# Radio.net
KiCad netlist of a schematic drawn in Altium Designer
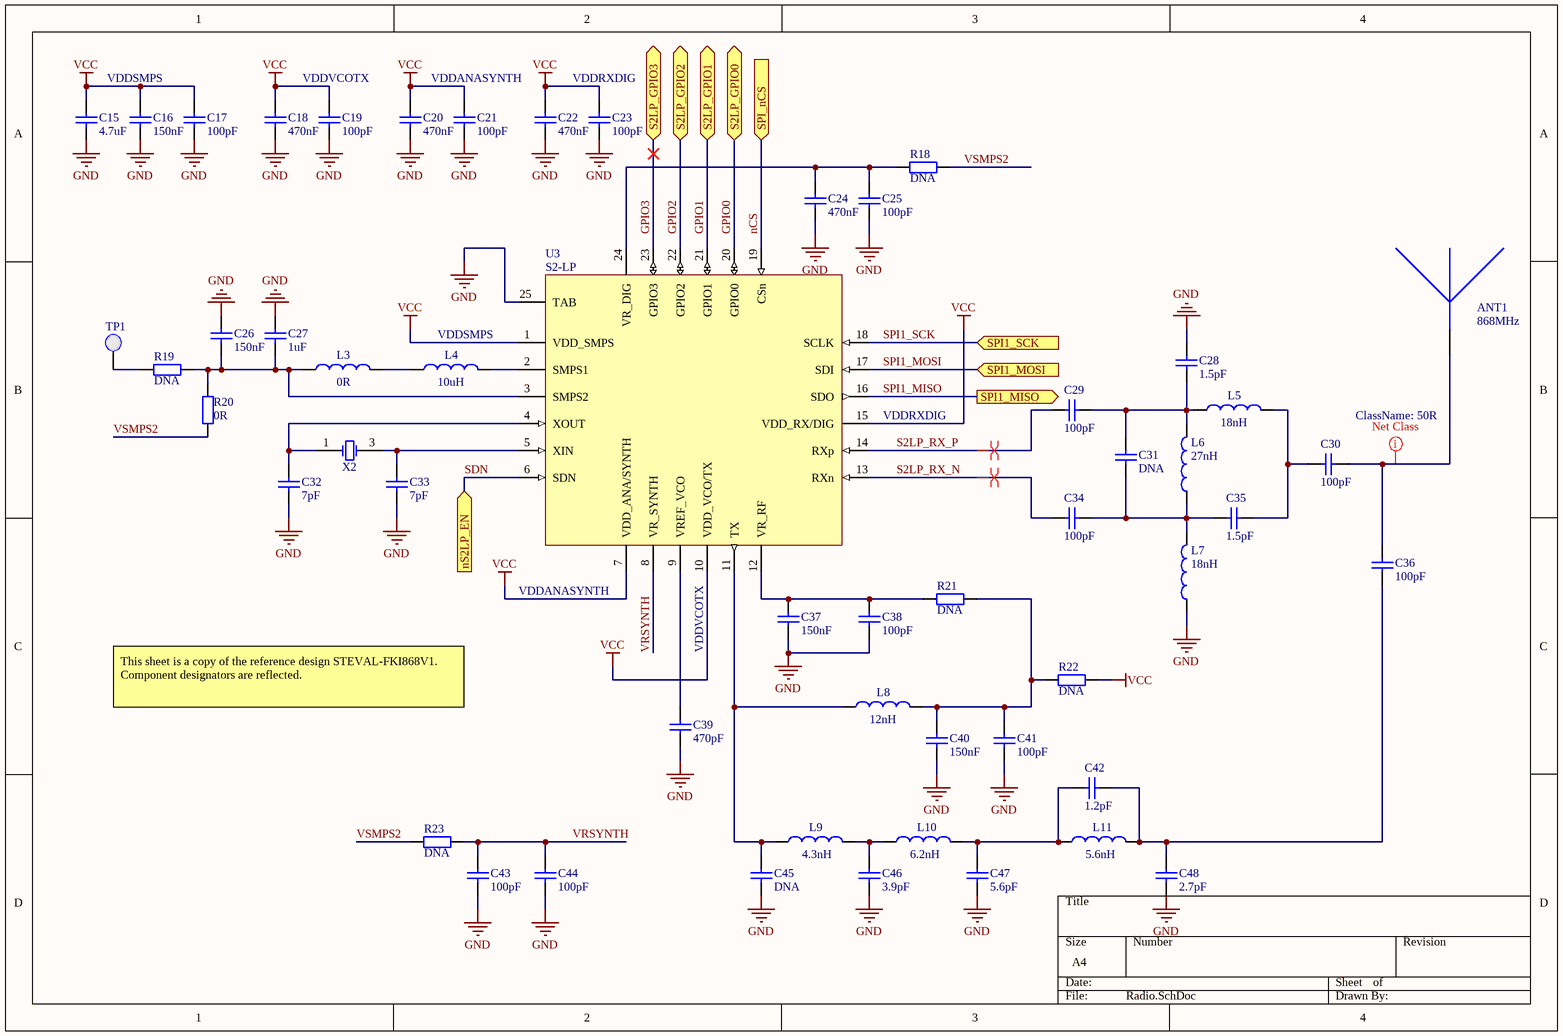
[diagram p0: Radio.SchDoc]

(export (version "E")
  (design (tool "Eeschema 10.0.6"))
  (components
    (comp (ref "ANT1")
      (value "868MHz")
      (footprint "ANTENNA")
      (libsource (lib "Light Sensor Node") (part "ANTENNA"))
    )
    (comp (ref "C15")
      (value "4.7uF")
      (footprint "C0603")
      (description "CAP")
      (fields
        (field (name "MANUFACTURER") "MURATA")
        (field (name "MANUFACTURER PART NUMBER") "GRM188R60J475KE19")
      )
      (libsource (lib "Light Sensor Node") (part "CAP"))
    )
    (comp (ref "C16")
      (value "150nF")
      (footprint "C0402")
      (description "CAP")
      (fields
        (field (name "MANUFACTURER") "MURATA")
        (field (name "MANUFACTURER PART NUMBER") "GRM155R61A154KE19")
      )
      (libsource (lib "Light Sensor Node") (part "CAP"))
    )
    (comp (ref "C17")
      (value "100pF")
      (footprint "C0402")
      (description "CAP")
      (fields
        (field (name "MANUFACTURER") "MURATA")
        (field (name "MANUFACTURER PART NUMBER") "GRM1555C1H101JA01D")
      )
      (libsource (lib "Light Sensor Node") (part "CAP"))
    )
    (comp (ref "C18")
      (value "470nF")
      (footprint "C0402")
      (description "CAP")
      (fields
        (field (name "MANUFACTURER") "MURATA")
        (field (name "MANUFACTURER PART NUMBER") "GRM155R61A474KE15")
      )
      (libsource (lib "Light Sensor Node") (part "CAP"))
    )
    (comp (ref "C19")
      (value "100pF")
      (footprint "C0402")
      (description "CAP")
      (fields
        (field (name "MANUFACTURER") "MURATA")
        (field (name "MANUFACTURER PART NUMBER") "GRM1555C1H101JA01D")
      )
      (libsource (lib "Light Sensor Node") (part "CAP"))
    )
    (comp (ref "C20")
      (value "470nF")
      (footprint "C0402")
      (description "CAP")
      (fields
        (field (name "MANUFACTURER") "MURATA")
        (field (name "MANUFACTURER PART NUMBER") "GRM155R61A474KE15")
      )
      (libsource (lib "Light Sensor Node") (part "CAP"))
    )
    (comp (ref "C21")
      (value "100pF")
      (footprint "C0402")
      (description "CAP")
      (fields
        (field (name "MANUFACTURER") "MURATA")
        (field (name "MANUFACTURER PART NUMBER") "GRM1555C1H101JA01D")
      )
      (libsource (lib "Light Sensor Node") (part "CAP"))
    )
    (comp (ref "C22")
      (value "470nF")
      (footprint "C0402")
      (description "CAP")
      (fields
        (field (name "MANUFACTURER") "MURATA")
        (field (name "MANUFACTURER PART NUMBER") "GRM155R61A474KE15")
      )
      (libsource (lib "Light Sensor Node") (part "CAP"))
    )
    (comp (ref "C23")
      (value "100pF")
      (footprint "C0402")
      (description "CAP")
      (fields
        (field (name "MANUFACTURER") "MURATA")
        (field (name "MANUFACTURER PART NUMBER") "GRM1555C1H101JA01D")
      )
      (libsource (lib "Light Sensor Node") (part "CAP"))
    )
    (comp (ref "C24")
      (value "470nF")
      (footprint "C0402")
      (description "CAP")
      (fields
        (field (name "MANUFACTURER") "MURATA")
        (field (name "MANUFACTURER PART NUMBER") "GRM155R61A474KE15")
      )
      (libsource (lib "Light Sensor Node") (part "CAP"))
    )
    (comp (ref "C25")
      (value "100pF")
      (footprint "C0402")
      (description "CAP")
      (fields
        (field (name "MANUFACTURER") "MURATA")
        (field (name "MANUFACTURER PART NUMBER") "GRM1555C1H101JA01D")
      )
      (libsource (lib "Light Sensor Node") (part "CAP"))
    )
    (comp (ref "C26")
      (value "150nF")
      (footprint "C0402")
      (description "CAP")
      (fields
        (field (name "MANUFACTURER") "MURATA")
        (field (name "MANUFACTURER PART NUMBER") "GRM155R61A154KE19")
      )
      (libsource (lib "Light Sensor Node") (part "CAP"))
    )
    (comp (ref "C27")
      (value "1uF")
      (footprint "C0603")
      (description "CAP")
      (fields
        (field (name "MANUFACTURER") "MURATA")
        (field (name "MANUFACTURER PART NUMBER") "GRM188R60J105KA01D")
      )
      (libsource (lib "Light Sensor Node") (part "CAP"))
    )
    (comp (ref "C28")
      (value "1.5pF")
      (footprint "C0402")
      (description "CAP")
      (fields
        (field (name "MANUFACTURER") "MURATA")
        (field (name "MANUFACTURER PART NUMBER") "GRM1555C1H1R5CA01D")
      )
      (libsource (lib "Light Sensor Node") (part "CAP"))
    )
    (comp (ref "C29")
      (value "100pF")
      (footprint "C0402")
      (description "CAP")
      (fields
        (field (name "MANUFACTURER") "MURATA")
        (field (name "MANUFACTURER PART NUMBER") "GRM1555C1H101JA01D")
      )
      (libsource (lib "Light Sensor Node") (part "CAP"))
    )
    (comp (ref "C30")
      (value "100pF")
      (footprint "C0402")
      (description "CAP")
      (fields
        (field (name "MANUFACTURER") "MURATA")
        (field (name "MANUFACTURER PART NUMBER") "GRM1555C1H101JA01D")
      )
      (libsource (lib "Light Sensor Node") (part "CAP"))
    )
    (comp (ref "C31") (value "DNA") (description "CAP") (libsource (lib "Light Sensor Node") (part "CAP")))
    (comp (ref "C32")
      (value "7pF")
      (footprint "C0805")
      (description "CAP")
      (fields
        (field (name "MANUFACTURER") "Yageo")
        (field (name "MANUFACTURER PART NUMBER") "CC0805DRNPO9BN7R0")
      )
      (libsource (lib "Light Sensor Node") (part "CAP"))
    )
    (comp (ref "C33")
      (value "7pF")
      (footprint "C0805")
      (description "CAP")
      (fields
        (field (name "MANUFACTURER") "Yageo")
        (field (name "MANUFACTURER PART NUMBER") "CC0805DRNPO9BN7R0")
      )
      (libsource (lib "Light Sensor Node") (part "CAP"))
    )
    (comp (ref "C34")
      (value "100pF")
      (footprint "C0402")
      (description "CAP")
      (fields
        (field (name "MANUFACTURER") "MURATA")
        (field (name "MANUFACTURER PART NUMBER") "GRM1555C1H101JA01D")
      )
      (libsource (lib "Light Sensor Node") (part "CAP"))
    )
    (comp (ref "C35")
      (value "1.5pF")
      (footprint "C0402")
      (description "CAP")
      (fields
        (field (name "MANUFACTURER") "MURATA")
        (field (name "MANUFACTURER PART NUMBER") "GRM1555C1H1R5CA01D")
      )
      (libsource (lib "Light Sensor Node") (part "CAP"))
    )
    (comp (ref "C36")
      (value "100pF")
      (footprint "C0402")
      (description "CAP")
      (fields
        (field (name "MANUFACTURER") "MURATA")
        (field (name "MANUFACTURER PART NUMBER") "GRM1555C1H101JA01D")
      )
      (libsource (lib "Light Sensor Node") (part "CAP"))
    )
    (comp (ref "C37")
      (value "150nF")
      (footprint "C0402")
      (description "CAP")
      (fields
        (field (name "MANUFACTURER") "MURATA")
        (field (name "MANUFACTURER PART NUMBER") "GRM155R61A154KE19")
      )
      (libsource (lib "Light Sensor Node") (part "CAP"))
    )
    (comp (ref "C38")
      (value "100pF")
      (footprint "C0402")
      (description "CAP")
      (fields
        (field (name "MANUFACTURER") "MURATA")
        (field (name "MANUFACTURER PART NUMBER") "GRM1555C1H101JA01D")
      )
      (libsource (lib "Light Sensor Node") (part "CAP"))
    )
    (comp (ref "C39")
      (value "470pF")
      (footprint "C0402")
      (description "CAP")
      (fields
        (field (name "MANUFACTURER") "Murata")
        (field (name "MANUFACTURER PART NUMBER") "GRM1555C1H471JA01")
      )
      (libsource (lib "Light Sensor Node") (part "CAP"))
    )
    (comp (ref "C40")
      (value "150nF")
      (footprint "C0402")
      (description "CAP")
      (fields
        (field (name "MANUFACTURER") "MURATA")
        (field (name "MANUFACTURER PART NUMBER") "GRM155R61A154KE19")
      )
      (libsource (lib "Light Sensor Node") (part "CAP"))
    )
    (comp (ref "C41")
      (value "100pF")
      (footprint "C0402")
      (description "CAP")
      (fields
        (field (name "MANUFACTURER") "MURATA")
        (field (name "MANUFACTURER PART NUMBER") "GRM1555C1H101JA01D")
      )
      (libsource (lib "Light Sensor Node") (part "CAP"))
    )
    (comp (ref "C42")
      (value "1.2pF")
      (footprint "C0402")
      (description "CAP")
      (fields
        (field (name "MANUFACTURER") "MURATA")
        (field (name "MANUFACTURER PART NUMBER") "GRM1555C1H1R2CA01D")
      )
      (libsource (lib "Light Sensor Node") (part "CAP"))
    )
    (comp (ref "C43")
      (value "100pF")
      (footprint "C0402")
      (description "CAP")
      (fields
        (field (name "MANUFACTURER") "MURATA")
        (field (name "MANUFACTURER PART NUMBER") "GRM1555C1H101JA01D")
      )
      (libsource (lib "Light Sensor Node") (part "CAP"))
    )
    (comp (ref "C44")
      (value "100pF")
      (footprint "C0402")
      (description "CAP")
      (fields
        (field (name "MANUFACTURER") "MURATA")
        (field (name "MANUFACTURER PART NUMBER") "GRM1555C1H101JA01D")
      )
      (libsource (lib "Light Sensor Node") (part "CAP"))
    )
    (comp (ref "C45")
      (value "DNA")
      (footprint "C0402")
      (description "CAP")
      (libsource (lib "Light Sensor Node") (part "CAP"))
    )
    (comp (ref "C46")
      (value "3.9pF")
      (footprint "C0402")
      (description "CAP")
      (fields
        (field (name "MANUFACTURER") "MURATA")
        (field (name "MANUFACTURER PART NUMBER") "GRM1555C1H3R9CA01D")
      )
      (libsource (lib "Light Sensor Node") (part "CAP"))
    )
    (comp (ref "C47")
      (value "5.6pF")
      (footprint "C0402")
      (description "CAP")
      (fields
        (field (name "MANUFACTURER") "MURATA")
        (field (name "MANUFACTURER PART NUMBER") "GRM1555C1H5R6CA01D")
      )
      (libsource (lib "Light Sensor Node") (part "CAP"))
    )
    (comp (ref "C48")
      (value "2.7pF")
      (footprint "C0402")
      (description "CAP")
      (fields
        (field (name "MANUFACTURER") "MURATA")
        (field (name "MANUFACTURER PART NUMBER") "GRM1555C1H2R7BA01D")
      )
      (libsource (lib "Light Sensor Node") (part "CAP"))
    )
    (comp (ref "L3")
      (value "0R")
      (footprint "R0402")
      (fields
        (field (name "MANUFACTURER") "TE Connectivity")
        (field (name "MANUFACTURER PART NUMBER") "CRG0402ZR")
      )
      (libsource (lib "Light Sensor Node") (part "IND"))
    )
    (comp (ref "L4")
      (value "IND")
      (footprint "R0805")
      (fields
        (field (name "MANUFACTURER") "MURATA")
        (field (name "MANUFACTURER PART NUMBER") "LQM21FN100M70L")
        (field (name "INDUCTANCE") "10uH")
      )
      (libsource (lib "Light Sensor Node") (part "IND"))
    )
    (comp (ref "L5")
      (value "IND")
      (footprint "R0603")
      (fields
        (field (name "MANUFACTURER") "MURATA")
        (field (name "MANUFACTURER PART NUMBER") "LQG15HS18NJ02D")
        (field (name "INDUCTANCE") "18nH")
      )
      (libsource (lib "Light Sensor Node") (part "IND"))
    )
    (comp (ref "L6")
      (value "IND")
      (footprint "R0603")
      (fields
        (field (name "MANUFACTURER") "MURATA")
        (field (name "MANUFACTURER PART NUMBER") "LQG15HS27NJ02D")
        (field (name "INDUCTANCE") "27nH")
      )
      (libsource (lib "") (part "IND_1"))
    )
    (comp (ref "L7")
      (value "IND")
      (footprint "R0603")
      (fields
        (field (name "MANUFACTURER") "MURATA")
        (field (name "MANUFACTURER PART NUMBER") "LQG15HS18NJ02D")
        (field (name "INDUCTANCE") "18nH")
      )
      (libsource (lib "") (part "IND_1"))
    )
    (comp (ref "L8")
      (value "IND")
      (footprint "R0603")
      (fields
        (field (name "MANUFACTURER") "MURATA")
        (field (name "MANUFACTURER PART NUMBER") "LQG18HN12NJ00D")
        (field (name "INDUCTANCE") "12nH")
      )
      (libsource (lib "Light Sensor Node") (part "IND"))
    )
    (comp (ref "L9")
      (value "IND")
      (footprint "R0402")
      (fields
        (field (name "MANUFACTURER") "MURATA")
        (field (name "MANUFACTURER PART NUMBER") "LQG15HS4N3S02D")
        (field (name "INDUCTANCE") "4.3nH")
      )
      (libsource (lib "Light Sensor Node") (part "IND"))
    )
    (comp (ref "L10")
      (value "IND")
      (footprint "R0402")
      (fields
        (field (name "MANUFACTURER") "MURATA")
        (field (name "MANUFACTURER PART NUMBER") "LQG15HN6N2S02D")
        (field (name "INDUCTANCE") "6.2nH")
      )
      (libsource (lib "Light Sensor Node") (part "IND"))
    )
    (comp (ref "L11")
      (value "IND")
      (footprint "R0805")
      (fields
        (field (name "MANUFACTURER") "MURATA")
        (field (name "MANUFACTURER PART NUMBER") "LQW2BAS5N6J00L")
        (field (name "INDUCTANCE") "5.6nH")
      )
      (libsource (lib "Light Sensor Node") (part "IND"))
    )
    (comp (ref "R18")
      (value "DNA")
      (footprint "R0402")
      (description "RES")
      (libsource (lib "Light Sensor Node") (part "RES"))
    )
    (comp (ref "R19")
      (value "DNA")
      (footprint "R0402")
      (description "RES")
      (libsource (lib "Light Sensor Node") (part "RES"))
    )
    (comp (ref "R20")
      (value "0R")
      (footprint "R0402")
      (description "RES")
      (fields (field (name "MANUFACTURER") "TE Connectivity"))
      (libsource (lib "") (part "RES_1"))
    )
    (comp (ref "R21")
      (value "DNA")
      (footprint "R0402")
      (description "RES")
      (libsource (lib "Light Sensor Node") (part "RES"))
    )
    (comp (ref "R22")
      (value "DNA")
      (footprint "R0402")
      (description "RES")
      (libsource (lib "Light Sensor Node") (part "RES"))
    )
    (comp (ref "R23")
      (value "DNA")
      (footprint "R0402")
      (description "RES")
      (libsource (lib "Light Sensor Node") (part "RES"))
    )
    (comp (ref "TP1")
      (value "TP_1mm")
      (footprint "TP_1mm")
      (libsource (lib "Light Sensor Node") (part "TP_1mm"))
    )
    (comp (ref "U3")
      (value "S2-LP")
      (footprint "ST_S2LP")
      (fields (field (name "MANUFACTURER") "ST Microelectronics"))
      (libsource (lib "Light Sensor Node") (part "ST_S2-LP"))
    )
    (comp (ref "X2")
      (value "50MHz")
      (footprint "ABRACON_ABMM2")
      (description "Crystal Oscillator")
      (fields
        (field (name "MANUFACTURER") "ABRACON")
        (field (name "MANUFACTURER PART NUMBER") "ABMM2-50.000MHZ-E2F-T")
      )
      (libsource (lib "Light Sensor Node") (part "OSC"))
    )
  )
  (nets
    (net (code "1") (name "/GPIO0") (class "Default")
      (node (ref "U3") (pin "20") (pinfunction "GPIO0_20") (pintype "bidirectional"))
    )
    (net (code "2") (name "/GPIO1") (class "Default")
      (node (ref "U3") (pin "21") (pinfunction "GPIO1_21") (pintype "bidirectional"))
    )
    (net (code "3") (name "/GPIO2") (class "Default")
      (node (ref "U3") (pin "22") (pinfunction "GPIO2_22") (pintype "bidirectional"))
    )
    (net (code "4") (name "/GPIO3") (class "Default")
      (node (ref "U3") (pin "23") (pinfunction "GPIO3_23") (pintype "bidirectional"))
    )
    (net (code "5") (name "/S2LP_RX_N") (class "Default")
      (node (ref "C34") (pin "2") (pinfunction "2_2") (pintype "passive"))
      (node (ref "U3") (pin "13") (pinfunction "RXn_13") (pintype "input"))
    )
    (net (code "6") (name "/S2LP_RX_P") (class "Default")
      (node (ref "C29") (pin "2") (pinfunction "2_2") (pintype "passive"))
      (node (ref "U3") (pin "14") (pinfunction "RXp_14") (pintype "input"))
    )
    (net (code "7") (name "/SDN") (class "Default")
      (node (ref "U3") (pin "6") (pinfunction "SDN_6") (pintype "input"))
    )
    (net (code "8") (name "/SPI1_MISO") (class "Default")
      (node (ref "U3") (pin "16") (pinfunction "SDO_16") (pintype "output"))
    )
    (net (code "9") (name "/SPI1_MOSI") (class "Default")
      (node (ref "U3") (pin "17") (pinfunction "SDI_17") (pintype "input"))
    )
    (net (code "10") (name "/SPI1_SCK") (class "Default")
      (node (ref "U3") (pin "18") (pinfunction "SCLK_18") (pintype "input"))
    )
    (net (code "11") (name "/VRSYNTH") (class "Default")
      (node (ref "C43") (pin "2") (pinfunction "2_2") (pintype "passive"))
      (node (ref "C44") (pin "2") (pinfunction "2_2") (pintype "passive"))
      (node (ref "R23") (pin "2") (pinfunction "2_2") (pintype "passive"))
      (node (ref "U3") (pin "8") (pinfunction "VR_SYNTH_8") (pintype "power_in"))
    )
    (net (code "12") (name "/VSMPS2") (class "Default")
      (node (ref "R18") (pin "2") (pinfunction "2_2") (pintype "passive"))
      (node (ref "R20") (pin "1") (pinfunction "1_1") (pintype "passive"))
      (node (ref "R23") (pin "1") (pinfunction "1_1") (pintype "passive"))
    )
    (net (code "13") (name "/nCS") (class "Default")
      (node (ref "U3") (pin "19") (pinfunction "CSn_19") (pintype "input"))
    )
    (net (code "14") (name "GND") (class "Default")
      (node (ref "C15") (pin "1") (pinfunction "1_1") (pintype "passive"))
      (node (ref "C16") (pin "1") (pinfunction "1_1") (pintype "passive"))
      (node (ref "C17") (pin "1") (pinfunction "1_1") (pintype "passive"))
      (node (ref "C18") (pin "1") (pinfunction "1_1") (pintype "passive"))
      (node (ref "C19") (pin "1") (pinfunction "1_1") (pintype "passive"))
      (node (ref "C20") (pin "1") (pinfunction "1_1") (pintype "passive"))
      (node (ref "C21") (pin "1") (pinfunction "1_1") (pintype "passive"))
      (node (ref "C22") (pin "1") (pinfunction "1_1") (pintype "passive"))
      (node (ref "C23") (pin "1") (pinfunction "1_1") (pintype "passive"))
      (node (ref "C24") (pin "1") (pinfunction "1_1") (pintype "passive"))
      (node (ref "C25") (pin "1") (pinfunction "1_1") (pintype "passive"))
      (node (ref "C26") (pin "2") (pinfunction "2_2") (pintype "passive"))
      (node (ref "C27") (pin "2") (pinfunction "2_2") (pintype "passive"))
      (node (ref "C28") (pin "1") (pinfunction "1_1") (pintype "passive"))
      (node (ref "C32") (pin "1") (pinfunction "1_1") (pintype "passive"))
      (node (ref "C33") (pin "1") (pinfunction "1_1") (pintype "passive"))
      (node (ref "C37") (pin "1") (pinfunction "1_1") (pintype "passive"))
      (node (ref "C38") (pin "1") (pinfunction "1_1") (pintype "passive"))
      (node (ref "C39") (pin "1") (pinfunction "1_1") (pintype "passive"))
      (node (ref "C40") (pin "1") (pinfunction "1_1") (pintype "passive"))
      (node (ref "C41") (pin "1") (pinfunction "1_1") (pintype "passive"))
      (node (ref "C43") (pin "1") (pinfunction "1_1") (pintype "passive"))
      (node (ref "C44") (pin "1") (pinfunction "1_1") (pintype "passive"))
      (node (ref "C45") (pin "1") (pinfunction "1_1") (pintype "passive"))
      (node (ref "C46") (pin "1") (pinfunction "1_1") (pintype "passive"))
      (node (ref "C47") (pin "1") (pinfunction "1_1") (pintype "passive"))
      (node (ref "C48") (pin "1") (pinfunction "1_1") (pintype "passive"))
      (node (ref "L7") (pin "2") (pinfunction "2_2") (pintype "passive"))
      (node (ref "U3") (pin "25") (pinfunction "TAB_25") (pintype "power_in"))
    )
    (net (code "15") (name "Net-(ANT1-V+)") (class "Default")
      (node (ref "ANT1") (pin "1") (pinfunction "V+_1") (pintype "passive"))
      (node (ref "C30") (pin "1") (pinfunction "1_1") (pintype "passive"))
      (node (ref "C36") (pin "2") (pinfunction "2_2") (pintype "passive"))
    )
    (net (code "16") (name "Net-(C28-Pad2)") (class "Default")
      (node (ref "C28") (pin "2") (pinfunction "2_2") (pintype "passive"))
      (node (ref "C29") (pin "1") (pinfunction "1_1") (pintype "passive"))
      (node (ref "C31") (pin "2") (pinfunction "2_2") (pintype "passive"))
      (node (ref "L5") (pin "2") (pinfunction "2_2") (pintype "passive"))
      (node (ref "L6") (pin "1") (pinfunction "1_1") (pintype "passive"))
    )
    (net (code "17") (name "Net-(C30-Pad2)") (class "Default")
      (node (ref "C30") (pin "2") (pinfunction "2_2") (pintype "passive"))
      (node (ref "C35") (pin "1") (pinfunction "1_1") (pintype "passive"))
      (node (ref "L5") (pin "1") (pinfunction "1_1") (pintype "passive"))
    )
    (net (code "18") (name "Net-(C31-Pad1)") (class "Default")
      (node (ref "C31") (pin "1") (pinfunction "1_1") (pintype "passive"))
      (node (ref "C34") (pin "1") (pinfunction "1_1") (pintype "passive"))
      (node (ref "C35") (pin "2") (pinfunction "2_2") (pintype "passive"))
      (node (ref "L6") (pin "2") (pinfunction "2_2") (pintype "passive"))
      (node (ref "L7") (pin "1") (pinfunction "1_1") (pintype "passive"))
    )
    (net (code "19") (name "Net-(C36-Pad1)") (class "Default")
      (node (ref "C36") (pin "1") (pinfunction "1_1") (pintype "passive"))
      (node (ref "C42") (pin "1") (pinfunction "1_1") (pintype "passive"))
      (node (ref "C48") (pin "2") (pinfunction "2_2") (pintype "passive"))
      (node (ref "L11") (pin "1") (pinfunction "1_1") (pintype "passive"))
    )
    (net (code "20") (name "Net-(C40-Pad2)") (class "Default")
      (node (ref "C40") (pin "2") (pinfunction "2_2") (pintype "passive"))
      (node (ref "C41") (pin "2") (pinfunction "2_2") (pintype "passive"))
      (node (ref "L8") (pin "1") (pinfunction "1_1") (pintype "passive"))
      (node (ref "R21") (pin "2") (pinfunction "2_2") (pintype "passive"))
      (node (ref "R22") (pin "1") (pinfunction "1_1") (pintype "passive"))
    )
    (net (code "21") (name "Net-(C42-Pad2)") (class "Default")
      (node (ref "C42") (pin "2") (pinfunction "2_2") (pintype "passive"))
      (node (ref "C47") (pin "2") (pinfunction "2_2") (pintype "passive"))
      (node (ref "L10") (pin "1") (pinfunction "1_1") (pintype "passive"))
      (node (ref "L11") (pin "2") (pinfunction "2_2") (pintype "passive"))
    )
    (net (code "22") (name "Net-(C46-Pad2)") (class "Default")
      (node (ref "C46") (pin "2") (pinfunction "2_2") (pintype "passive"))
      (node (ref "L10") (pin "2") (pinfunction "2_2") (pintype "passive"))
      (node (ref "L9") (pin "1") (pinfunction "1_1") (pintype "passive"))
    )
    (net (code "23") (name "Net-(L3-Pad1)") (class "Default")
      (node (ref "L3") (pin "1") (pinfunction "1_1") (pintype "passive"))
      (node (ref "L4") (pin "2") (pinfunction "2_2") (pintype "passive"))
    )
    (net (code "24") (name "Net-(R19-Pad1)") (class "Default")
      (node (ref "R19") (pin "1") (pinfunction "1_1") (pintype "passive"))
      (node (ref "TP1") (pin "1") (pinfunction "1_1") (pintype "passive"))
    )
    (net (code "25") (name "Net-(U3-SMPS1)") (class "Default")
      (node (ref "L4") (pin "1") (pinfunction "1_1") (pintype "passive"))
      (node (ref "U3") (pin "2") (pinfunction "SMPS1_2") (pintype "power_in"))
    )
    (net (code "26") (name "Net-(U3-SMPS2)") (class "Default")
      (node (ref "C26") (pin "1") (pinfunction "1_1") (pintype "passive"))
      (node (ref "C27") (pin "1") (pinfunction "1_1") (pintype "passive"))
      (node (ref "L3") (pin "2") (pinfunction "2_2") (pintype "passive"))
      (node (ref "R19") (pin "2") (pinfunction "2_2") (pintype "passive"))
      (node (ref "R20") (pin "2") (pinfunction "2_2") (pintype "passive"))
      (node (ref "U3") (pin "3") (pinfunction "SMPS2_3") (pintype "power_in"))
    )
    (net (code "27") (name "Net-(U3-TX)") (class "Default")
      (node (ref "C45") (pin "2") (pinfunction "2_2") (pintype "passive"))
      (node (ref "L8") (pin "2") (pinfunction "2_2") (pintype "passive"))
      (node (ref "L9") (pin "2") (pinfunction "2_2") (pintype "passive"))
      (node (ref "U3") (pin "11") (pinfunction "TX_11") (pintype "output"))
    )
    (net (code "28") (name "Net-(U3-VREF_VCO)") (class "Default")
      (node (ref "C39") (pin "2") (pinfunction "2_2") (pintype "passive"))
      (node (ref "U3") (pin "9") (pinfunction "VREF_VCO_9") (pintype "power_in"))
    )
    (net (code "29") (name "Net-(U3-VR_DIG)") (class "Default")
      (node (ref "C24") (pin "2") (pinfunction "2_2") (pintype "passive"))
      (node (ref "C25") (pin "2") (pinfunction "2_2") (pintype "passive"))
      (node (ref "R18") (pin "1") (pinfunction "1_1") (pintype "passive"))
      (node (ref "U3") (pin "24") (pinfunction "VR_DIG_24") (pintype "power_in"))
    )
    (net (code "30") (name "Net-(U3-VR_RF)") (class "Default")
      (node (ref "C37") (pin "2") (pinfunction "2_2") (pintype "passive"))
      (node (ref "C38") (pin "2") (pinfunction "2_2") (pintype "passive"))
      (node (ref "R21") (pin "1") (pinfunction "1_1") (pintype "passive"))
      (node (ref "U3") (pin "12") (pinfunction "VR_RF_12") (pintype "power_in"))
    )
    (net (code "31") (name "Net-(U3-XIN)") (class "Default")
      (node (ref "C33") (pin "2") (pinfunction "2_2") (pintype "passive"))
      (node (ref "U3") (pin "5") (pinfunction "XIN_5") (pintype "input"))
      (node (ref "X2") (pin "3") (pinfunction "OSC2_3") (pintype "passive"))
    )
    (net (code "32") (name "Net-(U3-XOUT)") (class "Default")
      (node (ref "C32") (pin "2") (pinfunction "2_2") (pintype "passive"))
      (node (ref "U3") (pin "4") (pinfunction "XOUT_4") (pintype "input"))
      (node (ref "X2") (pin "1") (pinfunction "OSC1_1") (pintype "passive"))
    )
    (net (code "33") (name "VCC") (class "Default")
      (node (ref "C15") (pin "2") (pinfunction "2_2") (pintype "passive"))
      (node (ref "C16") (pin "2") (pinfunction "2_2") (pintype "passive"))
      (node (ref "C17") (pin "2") (pinfunction "2_2") (pintype "passive"))
      (node (ref "C18") (pin "2") (pinfunction "2_2") (pintype "passive"))
      (node (ref "C19") (pin "2") (pinfunction "2_2") (pintype "passive"))
      (node (ref "C20") (pin "2") (pinfunction "2_2") (pintype "passive"))
      (node (ref "C21") (pin "2") (pinfunction "2_2") (pintype "passive"))
      (node (ref "C22") (pin "2") (pinfunction "2_2") (pintype "passive"))
      (node (ref "C23") (pin "2") (pinfunction "2_2") (pintype "passive"))
      (node (ref "R22") (pin "2") (pinfunction "2_2") (pintype "passive"))
      (node (ref "U3") (pin "1") (pinfunction "VDD_SMPS_1") (pintype "power_in"))
      (node (ref "U3") (pin "10") (pinfunction "VDD_VCO/TX_10") (pintype "power_in"))
      (node (ref "U3") (pin "15") (pinfunction "VDD_RX/DIG_15") (pintype "power_in"))
      (node (ref "U3") (pin "7") (pinfunction "VDD_ANA/SYNTH_7") (pintype "power_in"))
    )
  )
)
